# Power_supply.net
KiCad netlist of a schematic drawn in Altium Designer
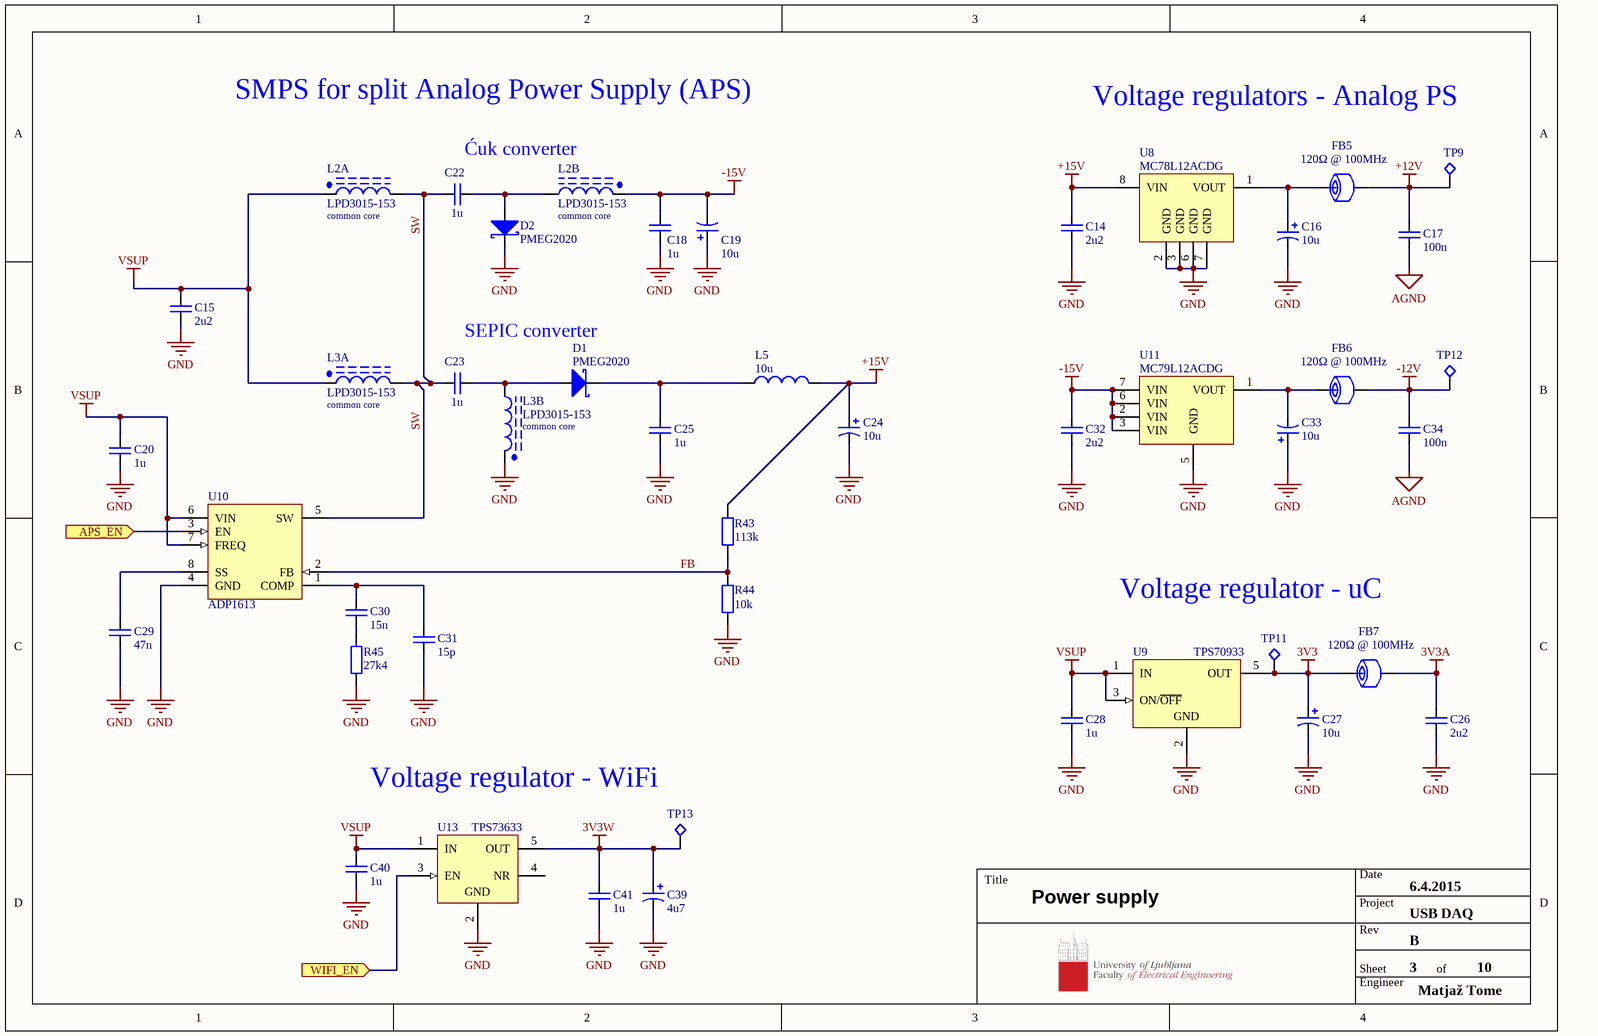
[diagram p0: Power_supply.SchDoc]

(export (version "E")
  (design (tool "Eeschema 10.0.6"))
  (components
    (comp (ref "C14")
      (value "2u2")
      (footprint "C_0603")
      (description "Generic capacitor")
      (fields (field (name "Comment") "comment"))
      (libsource (lib "DAQ") (part "Capacitor"))
    )
    (comp (ref "C15")
      (value "2u2")
      (footprint "C_0603")
      (description "Generic capacitor")
      (fields (field (name "Comment") "comment"))
      (libsource (lib "DAQ") (part "Capacitor"))
    )
    (comp (ref "C16")
      (value "10u")
      (footprint "Tantalum Case A")
      (description "Generic polarized capacitor")
      (fields (field (name "Comment") "comment"))
      (libsource (lib "DAQ") (part "Capacitor - polarized"))
    )
    (comp (ref "C17")
      (value "100n")
      (footprint "C_0603")
      (description "Generic capacitor")
      (fields (field (name "Comment") "comment"))
      (libsource (lib "DAQ") (part "Capacitor"))
    )
    (comp (ref "C18")
      (value "1u")
      (footprint "C_0603")
      (description "Generic capacitor")
      (fields (field (name "Comment") "comment"))
      (libsource (lib "DAQ") (part "Capacitor"))
    )
    (comp (ref "C19")
      (value "10u")
      (footprint "Tantalum Case A")
      (description "Generic polarized capacitor")
      (fields (field (name "Comment") "comment"))
      (libsource (lib "DAQ") (part "Capacitor - polarized"))
    )
    (comp (ref "C20")
      (value "1u")
      (footprint "C_0603")
      (description "Generic capacitor")
      (fields (field (name "Comment") "comment"))
      (libsource (lib "DAQ") (part "Capacitor"))
    )
    (comp (ref "C22")
      (value "1u")
      (footprint "C_0603")
      (description "Generic capacitor")
      (fields (field (name "Comment") "comment"))
      (libsource (lib "DAQ") (part "Capacitor"))
    )
    (comp (ref "C23")
      (value "1u")
      (footprint "C_0603")
      (description "Generic capacitor")
      (fields (field (name "Comment") "comment"))
      (libsource (lib "DAQ") (part "Capacitor"))
    )
    (comp (ref "C24")
      (value "10u")
      (footprint "Tantalum Case A")
      (description "Generic polarized capacitor")
      (fields (field (name "Comment") "comment"))
      (libsource (lib "DAQ") (part "Capacitor - polarized"))
    )
    (comp (ref "C25")
      (value "1u")
      (footprint "C_0603")
      (description "Generic capacitor")
      (fields (field (name "Comment") "comment"))
      (libsource (lib "DAQ") (part "Capacitor"))
    )
    (comp (ref "C26")
      (value "2u2")
      (footprint "C_0603")
      (description "Generic capacitor")
      (fields (field (name "Comment") "comment"))
      (libsource (lib "DAQ") (part "Capacitor"))
    )
    (comp (ref "C27")
      (value "10u")
      (footprint "Tantalum Case A")
      (description "Generic polarized capacitor")
      (fields (field (name "Comment") "comment"))
      (libsource (lib "DAQ") (part "Capacitor - polarized"))
    )
    (comp (ref "C28")
      (value "1u")
      (footprint "C_0603")
      (description "Generic capacitor")
      (fields (field (name "Comment") "comment"))
      (libsource (lib "DAQ") (part "Capacitor"))
    )
    (comp (ref "C29")
      (value "47n")
      (footprint "C_0603")
      (description "Generic capacitor")
      (fields (field (name "Comment") "comment"))
      (libsource (lib "DAQ") (part "Capacitor"))
    )
    (comp (ref "C30")
      (value "15n")
      (footprint "C_0603")
      (description "Generic capacitor")
      (fields (field (name "Comment") "comment"))
      (libsource (lib "DAQ") (part "Capacitor"))
    )
    (comp (ref "C31")
      (value "15p")
      (footprint "C_0603")
      (description "Generic capacitor")
      (fields (field (name "Comment") "comment"))
      (libsource (lib "DAQ") (part "Capacitor"))
    )
    (comp (ref "C32")
      (value "2u2")
      (footprint "C_0603")
      (description "Generic capacitor")
      (fields (field (name "Comment") "comment"))
      (libsource (lib "DAQ") (part "Capacitor"))
    )
    (comp (ref "C33")
      (value "10u")
      (footprint "Tantalum Case A")
      (description "Generic polarized capacitor")
      (fields (field (name "Comment") "comment"))
      (libsource (lib "DAQ") (part "Capacitor - polarized"))
    )
    (comp (ref "C34")
      (value "100n")
      (footprint "C_0603")
      (description "Generic capacitor")
      (fields (field (name "Comment") "comment"))
      (libsource (lib "DAQ") (part "Capacitor"))
    )
    (comp (ref "C39")
      (value "4u7")
      (footprint "Tantalum Case A")
      (description "Generic polarized capacitor")
      (fields (field (name "Comment") "comment"))
      (libsource (lib "DAQ") (part "Capacitor - polarized"))
    )
    (comp (ref "C40")
      (value "1u")
      (footprint "C_0603")
      (description "Generic capacitor")
      (fields (field (name "Comment") "comment"))
      (libsource (lib "DAQ") (part "Capacitor"))
    )
    (comp (ref "C41")
      (value "1u")
      (footprint "C_0603")
      (description "Generic capacitor")
      (fields (field (name "Comment") "comment"))
      (libsource (lib "DAQ") (part "Capacitor"))
    )
    (comp (ref "D1")
      (value "PMEG2020")
      (footprint "SOD323")
      (description "Schottky diode, 2A 20V")
      (fields (field (name "PART NUMBER") "XDS0004") (field (name "MANUFACTURER") "Infineon"))
      (libsource (lib "DAQ") (part "PMEG2020"))
    )
    (comp (ref "D2")
      (value "PMEG2020")
      (footprint "SOD323")
      (description "Schottky diode, 2A 20V")
      (fields (field (name "PART NUMBER") "XDS0004") (field (name "MANUFACTURER") "Infineon"))
      (libsource (lib "DAQ") (part "PMEG2020"))
    )
    (comp (ref "FB5")
      (value "120Ω @ 100MHz")
      (footprint "SMD_0805")
      (description "Ferrite Bead, 0805 [2012 Metric], 120 ohm, 800 mA, BLM21A Series, 0.15 ohm, ± 25%")
      (fields (field (name "MANUFACTURER") "Murata"))
      (libsource (lib "DAQ") (part "BLM21AG121SN1D"))
    )
    (comp (ref "FB6")
      (value "120Ω @ 100MHz")
      (footprint "SMD_0805")
      (description "Ferrite Bead, 0805 [2012 Metric], 120 ohm, 800 mA, BLM21A Series, 0.15 ohm, ± 25%")
      (fields (field (name "MANUFACTURER") "Murata"))
      (libsource (lib "DAQ") (part "BLM21AG121SN1D"))
    )
    (comp (ref "FB7")
      (value "120Ω @ 100MHz")
      (footprint "SMD_0805")
      (description "Ferrite Bead, 0805 [2012 Metric], 120 ohm, 800 mA, BLM21A Series, 0.15 ohm, ± 25%")
      (fields (field (name "MANUFACTURER") "Murata"))
      (libsource (lib "DAQ") (part "BLM21AG121SN1D"))
    )
    (comp (ref "L2")
      (value "LPD3015-153")
      (footprint "LPD3015")
      (description "Inductor, Coupled, 15 µH, 20%, 1.42 ohm, 460 mA, 3mm x 3mm x 1.4mm")
      (fields
        (field (name "MANUFACTURER") "Coilcraft")
        (field (name "TOLERANCE") "20%")
        (field (name "NOTE") "common core")
      )
      (libsource (lib "DAQ") (part "LPD3015-153"))
    )
    (comp (ref "L3")
      (value "LPD3015-153")
      (footprint "LPD3015")
      (description "Inductor, Coupled, 15 µH, 20%, 1.42 ohm, 460 mA, 3mm x 3mm x 1.4mm")
      (fields
        (field (name "MANUFACTURER") "Coilcraft")
        (field (name "TOLERANCE") "20%")
        (field (name "NOTE") "common core")
      )
      (libsource (lib "") (part "LPD3015-153_1"))
    )
    (comp (ref "L5")
      (value "10u")
      (footprint "IND_SMD_4X4mm")
      (description "Power Inductor (SMD), 10 µH, 770 mA, Shielded, 800 mA, TYS Series, 4mm x 4mm x 1.2mm")
      (fields (field (name "MANUFACTURER") "Laird Technologies") (field (name "TOLERANCE") "20%"))
      (libsource (lib "DAQ") (part "TYS4012100M-10"))
    )
    (comp (ref "R43")
      (value "113k")
      (footprint "R_0603")
      (description "Generic resistor")
      (fields (field (name "Comment") "comment"))
      (libsource (lib "DAQ") (part "Resistor"))
    )
    (comp (ref "R44")
      (value "10k")
      (footprint "R_0603")
      (description "Generic resistor")
      (fields (field (name "Comment") "comment"))
      (libsource (lib "DAQ") (part "Resistor"))
    )
    (comp (ref "R45")
      (value "27k4")
      (footprint "R_0603")
      (description "Generic resistor")
      (fields (field (name "Comment") "comment"))
      (libsource (lib "DAQ") (part "Resistor"))
    )
    (comp (ref "TP9")
      (value "testpoint")
      (footprint "TP1_FULL")
      (description "testpoint 1.5mm diameter no hole")
      (fields (field (name "PART NUMBER") "XXC0006"))
      (libsource (lib "DAQ") (part "Test Point"))
    )
    (comp (ref "TP11")
      (value "testpoint")
      (footprint "TP1_FULL")
      (description "testpoint 1.5mm diameter no hole")
      (fields (field (name "PART NUMBER") "XXC0006"))
      (libsource (lib "DAQ") (part "Test Point"))
    )
    (comp (ref "TP12")
      (value "testpoint")
      (footprint "TP1_FULL")
      (description "testpoint 1.5mm diameter no hole")
      (fields (field (name "PART NUMBER") "XXC0006"))
      (libsource (lib "DAQ") (part "Test Point"))
    )
    (comp (ref "TP13")
      (value "testpoint")
      (footprint "TP1_FULL")
      (description "testpoint 1.5mm diameter no hole")
      (fields (field (name "PART NUMBER") "XXC0006"))
      (libsource (lib "DAQ") (part "Test Point"))
    )
    (comp (ref "U8")
      (value "MC78L12ACDG")
      (footprint "SOIC8")
      (description "100 mA Positive Voltage Regulator")
      (fields (field (name "PART NUMBER") "XLR0006") (field (name "MANUFACTURER") "ON Semiconductors"))
      (libsource (lib "DAQ") (part "78LXX"))
    )
    (comp (ref "U9")
      (value "TPS70933")
      (footprint "SOT23-5")
      (description "1-µA IQ Voltage Regulators with Enable")
      (fields (field (name "PART NUMBER") "XLR0012") (field (name "MANUFACTURER") "Texas Instruments"))
      (libsource (lib "DAQ") (part "TPS709XX"))
    )
    (comp (ref "U10")
      (value "ADP1613")
      (footprint "MSOP8")
      (fields (field (name "PART NUMBER") "XSW0008") (field (name "MANUFACTURER") "Analog devices"))
      (libsource (lib "DAQ") (part "ADP161X"))
    )
    (comp (ref "U11")
      (value "MC79L12ACDG")
      (footprint "SOIC8")
      (description "100 mA Negative Voltage Regulator")
      (fields (field (name "PART NUMBER") "XLR0007") (field (name "MANUFACTURER") "ON Semiconductors"))
      (libsource (lib "DAQ") (part "79LXX"))
    )
    (comp (ref "U13")
      (value "TPS73633")
      (footprint "SOT23-5")
      (description "Cap-Free, NMOS, 400-mA Low-Dropout Regulator with Reverse Current Protection")
      (fields (field (name "PART NUMBER") "XLR0013") (field (name "MANUFACTURER") "Texas instruments"))
      (libsource (lib "DAQ") (part "TPS736XX"))
    )
  )
  (nets
    (net (code "1") (name "+12V") (class "Default")
      (node (ref "C17") (pin "2") (pinfunction "2_2") (pintype "passive"))
      (node (ref "FB5") (pin "2") (pintype "passive"))
      (node (ref "TP9") (pin "1") (pinfunction "1_1") (pintype "passive"))
    )
    (net (code "2") (name "+15V") (class "Default")
      (node (ref "C14") (pin "1") (pinfunction "1_1") (pintype "passive"))
      (node (ref "C24") (pin "1") (pinfunction "1_1") (pintype "passive"))
      (node (ref "L5") (pin "2") (pinfunction "2_2") (pintype "passive"))
      (node (ref "R43") (pin "1") (pintype "passive"))
      (node (ref "U8") (pin "8") (pinfunction "VIN_8") (pintype "power_in"))
    )
    (net (code "3") (name "-12V") (class "Default")
      (node (ref "C34") (pin "2") (pinfunction "2_2") (pintype "passive"))
      (node (ref "FB6") (pin "2") (pintype "passive"))
      (node (ref "TP12") (pin "1") (pinfunction "1_1") (pintype "passive"))
    )
    (net (code "4") (name "-15V") (class "Default")
      (node (ref "C18") (pin "1") (pinfunction "1_1") (pintype "passive"))
      (node (ref "C19") (pin "2") (pinfunction "2_2") (pintype "passive"))
      (node (ref "C32") (pin "1") (pinfunction "1_1") (pintype "passive"))
      (node (ref "L2") (pin "4") (pinfunction "4_4") (pintype "passive"))
      (node (ref "U11") (pin "2") (pinfunction "VIN_2") (pintype "power_in"))
      (node (ref "U11") (pin "3") (pinfunction "VIN_3") (pintype "power_in"))
      (node (ref "U11") (pin "6") (pinfunction "VIN_6") (pintype "power_in"))
      (node (ref "U11") (pin "7") (pinfunction "VIN_7") (pintype "power_in"))
    )
    (net (code "5") (name "/APS_EN") (class "Default")
      (node (ref "U10") (pin "3") (pinfunction "EN_3") (pintype "input"))
    )
    (net (code "6") (name "/FB") (class "Default")
      (node (ref "R43") (pin "2") (pintype "passive"))
      (node (ref "R44") (pin "2") (pintype "passive"))
      (node (ref "U10") (pin "2") (pinfunction "FB_2") (pintype "input"))
    )
    (net (code "7") (name "/SW") (class "Default")
      (node (ref "C22") (pin "1") (pinfunction "1_1") (pintype "passive"))
      (node (ref "C23") (pin "1") (pinfunction "1_1") (pintype "passive"))
      (node (ref "L2") (pin "2") (pinfunction "2_2") (pintype "passive"))
      (node (ref "L3") (pin "2") (pinfunction "2_2") (pintype "passive"))
      (node (ref "U10") (pin "5") (pinfunction "SW_5") (pintype "passive"))
    )
    (net (code "8") (name "/WIFI_EN") (class "Default")
      (node (ref "U13") (pin "3") (pinfunction "EN_3") (pintype "input"))
    )
    (net (code "9") (name "3V3") (class "Default")
      (node (ref "C27") (pin "1") (pinfunction "1_1") (pintype "passive"))
      (node (ref "FB7") (pin "1") (pintype "passive"))
      (node (ref "TP11") (pin "1") (pinfunction "1_1") (pintype "passive"))
      (node (ref "U9") (pin "5") (pinfunction "OUT_5") (pintype "power_in"))
    )
    (net (code "10") (name "3V3A") (class "Default")
      (node (ref "C26") (pin "1") (pinfunction "1_1") (pintype "passive"))
      (node (ref "FB7") (pin "2") (pintype "passive"))
    )
    (net (code "11") (name "3V3W") (class "Default")
      (node (ref "C39") (pin "1") (pinfunction "1_1") (pintype "passive"))
      (node (ref "C41") (pin "1") (pinfunction "1_1") (pintype "passive"))
      (node (ref "TP13") (pin "1") (pinfunction "1_1") (pintype "passive"))
      (node (ref "U13") (pin "5") (pinfunction "OUT_5") (pintype "power_in"))
    )
    (net (code "12") (name "AGND") (class "Default")
      (node (ref "C17") (pin "1") (pinfunction "1_1") (pintype "passive"))
      (node (ref "C34") (pin "1") (pinfunction "1_1") (pintype "passive"))
    )
    (net (code "13") (name "GND") (class "Default")
      (node (ref "C14") (pin "2") (pinfunction "2_2") (pintype "passive"))
      (node (ref "C15") (pin "1") (pinfunction "1_1") (pintype "passive"))
      (node (ref "C16") (pin "2") (pinfunction "2_2") (pintype "passive"))
      (node (ref "C18") (pin "2") (pinfunction "2_2") (pintype "passive"))
      (node (ref "C19") (pin "1") (pinfunction "1_1") (pintype "passive"))
      (node (ref "C20") (pin "2") (pinfunction "2_2") (pintype "passive"))
      (node (ref "C24") (pin "2") (pinfunction "2_2") (pintype "passive"))
      (node (ref "C25") (pin "2") (pinfunction "2_2") (pintype "passive"))
      (node (ref "C26") (pin "2") (pinfunction "2_2") (pintype "passive"))
      (node (ref "C27") (pin "2") (pinfunction "2_2") (pintype "passive"))
      (node (ref "C28") (pin "2") (pinfunction "2_2") (pintype "passive"))
      (node (ref "C29") (pin "2") (pinfunction "2_2") (pintype "passive"))
      (node (ref "C31") (pin "2") (pinfunction "2_2") (pintype "passive"))
      (node (ref "C32") (pin "2") (pinfunction "2_2") (pintype "passive"))
      (node (ref "C33") (pin "1") (pinfunction "1_1") (pintype "passive"))
      (node (ref "C39") (pin "2") (pinfunction "2_2") (pintype "passive"))
      (node (ref "C40") (pin "2") (pinfunction "2_2") (pintype "passive"))
      (node (ref "C41") (pin "2") (pinfunction "2_2") (pintype "passive"))
      (node (ref "D2") (pin "2") (pinfunction "K_2") (pintype "passive"))
      (node (ref "L3") (pin "4") (pinfunction "4_4") (pintype "passive"))
      (node (ref "R44") (pin "1") (pintype "passive"))
      (node (ref "R45") (pin "1") (pintype "passive"))
      (node (ref "U10") (pin "4") (pinfunction "GND_4") (pintype "power_in"))
      (node (ref "U11") (pin "5") (pinfunction "GND_5") (pintype "power_in"))
      (node (ref "U13") (pin "2") (pinfunction "GND_2") (pintype "power_in"))
      (node (ref "U8") (pin "2") (pinfunction "GND_2") (pintype "power_in"))
      (node (ref "U8") (pin "3") (pinfunction "GND_3") (pintype "power_in"))
      (node (ref "U8") (pin "6") (pinfunction "GND_6") (pintype "power_in"))
      (node (ref "U8") (pin "7") (pinfunction "GND_7") (pintype "power_in"))
      (node (ref "U9") (pin "2") (pinfunction "GND_2") (pintype "power_in"))
    )
    (net (code "14") (name "Net-(C30-Pad2)") (class "Default")
      (node (ref "C30") (pin "2") (pinfunction "2_2") (pintype "passive"))
      (node (ref "R45") (pin "2") (pintype "passive"))
    )
    (net (code "15") (name "Net-(D1-A)") (class "Default")
      (node (ref "C23") (pin "2") (pinfunction "2_2") (pintype "passive"))
      (node (ref "D1") (pin "1") (pinfunction "A_1") (pintype "passive"))
      (node (ref "L3") (pin "3") (pinfunction "3_3") (pintype "passive"))
    )
    (net (code "16") (name "Net-(D1-K)") (class "Default")
      (node (ref "C25") (pin "1") (pinfunction "1_1") (pintype "passive"))
      (node (ref "D1") (pin "2") (pinfunction "K_2") (pintype "passive"))
      (node (ref "L5") (pin "1") (pinfunction "1_1") (pintype "passive"))
    )
    (net (code "17") (name "Net-(D2-A)") (class "Default")
      (node (ref "C22") (pin "2") (pinfunction "2_2") (pintype "passive"))
      (node (ref "D2") (pin "1") (pinfunction "A_1") (pintype "passive"))
      (node (ref "L2") (pin "3") (pinfunction "3_3") (pintype "passive"))
    )
    (net (code "18") (name "Net-(U8-VOUT)") (class "Default")
      (node (ref "C16") (pin "1") (pinfunction "1_1") (pintype "passive"))
      (node (ref "FB5") (pin "1") (pintype "passive"))
      (node (ref "U8") (pin "1") (pinfunction "VOUT_1") (pintype "power_in"))
    )
    (net (code "19") (name "Net-(U10-COMP)") (class "Default")
      (node (ref "C30") (pin "1") (pinfunction "1_1") (pintype "passive"))
      (node (ref "C31") (pin "1") (pinfunction "1_1") (pintype "passive"))
      (node (ref "U10") (pin "1") (pinfunction "COMP_1") (pintype "passive"))
    )
    (net (code "20") (name "Net-(U10-SS)") (class "Default")
      (node (ref "C29") (pin "1") (pinfunction "1_1") (pintype "passive"))
      (node (ref "U10") (pin "8") (pinfunction "SS_8") (pintype "passive"))
    )
    (net (code "21") (name "Net-(U11-VOUT)") (class "Default")
      (node (ref "C33") (pin "2") (pinfunction "2_2") (pintype "passive"))
      (node (ref "FB6") (pin "1") (pintype "passive"))
      (node (ref "U11") (pin "1") (pinfunction "VOUT_1") (pintype "power_in"))
    )
    (net (code "22") (name "VSUP") (class "Default")
      (node (ref "C15") (pin "2") (pinfunction "2_2") (pintype "passive"))
      (node (ref "C20") (pin "1") (pinfunction "1_1") (pintype "passive"))
      (node (ref "C28") (pin "1") (pinfunction "1_1") (pintype "passive"))
      (node (ref "C40") (pin "1") (pinfunction "1_1") (pintype "passive"))
      (node (ref "L2") (pin "1") (pinfunction "1_1") (pintype "passive"))
      (node (ref "L3") (pin "1") (pinfunction "1_1") (pintype "passive"))
      (node (ref "U10") (pin "6") (pinfunction "VIN_6") (pintype "power_in"))
      (node (ref "U10") (pin "7") (pinfunction "FREQ_7") (pintype "input"))
      (node (ref "U13") (pin "1") (pinfunction "IN_1") (pintype "power_in"))
      (node (ref "U9") (pin "1") (pinfunction "IN_1") (pintype "power_in"))
      (node (ref "U9") (pin "3") (pinfunction "ON/~{OFF}_3") (pintype "input"))
    )
    (net (code "23") (name "unconnected-(U13-NR-Pad4)") (class "Default")
      (node (ref "U13") (pin "4") (pinfunction "NR_4") (pintype "passive"))
    )
  )
)
